# MCU.net
KiCad netlist of a schematic drawn in Altium Designer
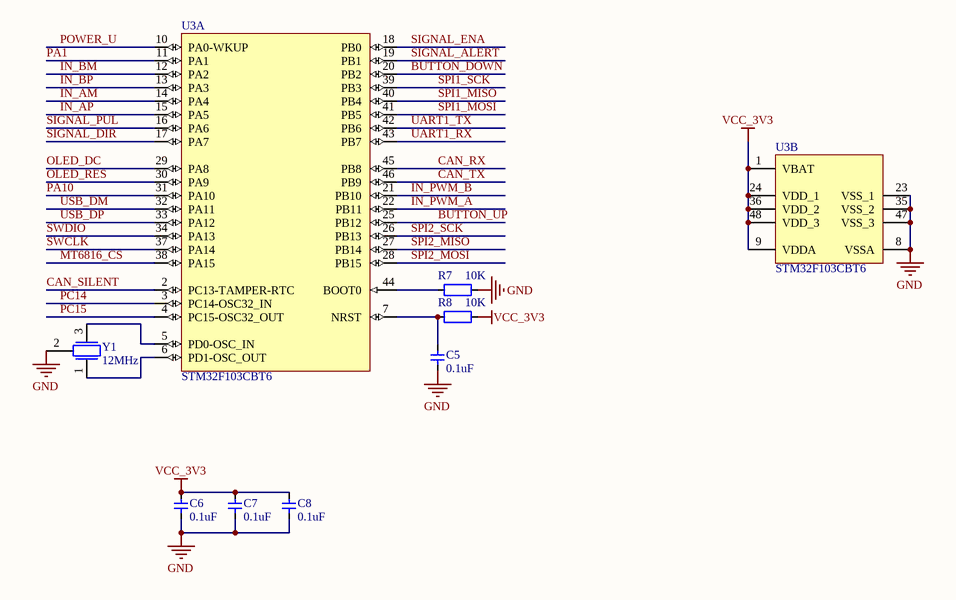
[diagram p0: MCU.SchDoc]

(export (version "E")
  (design (tool "Eeschema 10.0.6"))
  (components
    (comp (ref "C5")
      (value "0.1uF")
      (footprint "CAP_0402")
      (description "Capacitor")
      (libsource (lib "MyPcbLib") (part "电容-0402"))
    )
    (comp (ref "C6")
      (value "0.1uF")
      (footprint "CAP_0402")
      (description "Capacitor")
      (libsource (lib "MyPcbLib") (part "电容-0402"))
    )
    (comp (ref "C7")
      (value "0.1uF")
      (footprint "CAP_0402")
      (description "Capacitor")
      (libsource (lib "MyPcbLib") (part "电容-0402"))
    )
    (comp (ref "C8")
      (value "0.1uF")
      (footprint "CAP_0402")
      (description "Capacitor")
      (libsource (lib "MyPcbLib") (part "电容-0402"))
    )
    (comp (ref "R7")
      (value "10K")
      (footprint "RES_0402")
      (description "Resistor")
      (libsource (lib "MyPcbLib") (part "电阻-0402"))
    )
    (comp (ref "R8")
      (value "10K")
      (footprint "RES_0402")
      (description "Resistor")
      (libsource (lib "MyPcbLib") (part "电阻-0402"))
    )
    (comp (ref "U3")
      (value "STM32F103CBT6")
      (footprint "LQFP-48")
      (libsource (lib "STMicroelectronics STM32 F1") (part "STM32F103CBT6"))
    )
    (comp (ref "Y1")
      (value "12MHz")
      (footprint "晶振-3P")
      (description "村田贴片")
      (libsource (lib "MyPcbLib") (part "晶振-3Pin"))
    )
  )
  (nets
    (net (code "1") (name "/BUTTON_DOWN") (class "Default")
      (node (ref "U3") (pin "20") (pinfunction "PB2_20") (pintype "bidirectional"))
    )
    (net (code "2") (name "/BUTTON_UP") (class "Default")
      (node (ref "U3") (pin "25") (pinfunction "PB12_25") (pintype "bidirectional"))
    )
    (net (code "3") (name "/CAN_RX") (class "Default")
      (node (ref "U3") (pin "45") (pinfunction "PB8_45") (pintype "bidirectional"))
    )
    (net (code "4") (name "/CAN_SILENT") (class "Default")
      (node (ref "U3") (pin "2") (pinfunction "PC13-TAMPER-RTC_2") (pintype "bidirectional"))
    )
    (net (code "5") (name "/CAN_TX") (class "Default")
      (node (ref "U3") (pin "46") (pinfunction "PB9_46") (pintype "bidirectional"))
    )
    (net (code "6") (name "/IN_AM") (class "Default")
      (node (ref "U3") (pin "14") (pinfunction "PA4_14") (pintype "bidirectional"))
    )
    (net (code "7") (name "/IN_AP") (class "Default")
      (node (ref "U3") (pin "15") (pinfunction "PA5_15") (pintype "bidirectional"))
    )
    (net (code "8") (name "/IN_BM") (class "Default")
      (node (ref "U3") (pin "12") (pinfunction "PA2_12") (pintype "bidirectional"))
    )
    (net (code "9") (name "/IN_BP") (class "Default")
      (node (ref "U3") (pin "13") (pinfunction "PA3_13") (pintype "bidirectional"))
    )
    (net (code "10") (name "/IN_PWM_A") (class "Default")
      (node (ref "U3") (pin "22") (pinfunction "PB11_22") (pintype "bidirectional"))
    )
    (net (code "11") (name "/IN_PWM_B") (class "Default")
      (node (ref "U3") (pin "21") (pinfunction "PB10_21") (pintype "bidirectional"))
    )
    (net (code "12") (name "/MT6816_CS") (class "Default")
      (node (ref "U3") (pin "38") (pinfunction "PA15_38") (pintype "bidirectional"))
    )
    (net (code "13") (name "/OLED_DC") (class "Default")
      (node (ref "U3") (pin "29") (pinfunction "PA8_29") (pintype "bidirectional"))
    )
    (net (code "14") (name "/OLED_RES") (class "Default")
      (node (ref "U3") (pin "30") (pinfunction "PA9_30") (pintype "bidirectional"))
    )
    (net (code "15") (name "/PA1") (class "Default")
      (node (ref "U3") (pin "11") (pinfunction "PA1_11") (pintype "bidirectional"))
    )
    (net (code "16") (name "/PA10") (class "Default")
      (node (ref "U3") (pin "31") (pinfunction "PA10_31") (pintype "bidirectional"))
    )
    (net (code "17") (name "/PC14") (class "Default")
      (node (ref "U3") (pin "3") (pinfunction "PC14-OSC32_IN_3") (pintype "bidirectional"))
    )
    (net (code "18") (name "/PC15") (class "Default")
      (node (ref "U3") (pin "4") (pinfunction "PC15-OSC32_OUT_4") (pintype "bidirectional"))
    )
    (net (code "19") (name "/POWER_U") (class "Default")
      (node (ref "U3") (pin "10") (pinfunction "PA0-WKUP_10") (pintype "bidirectional"))
    )
    (net (code "20") (name "/SIGNAL_ALERT") (class "Default")
      (node (ref "U3") (pin "19") (pinfunction "PB1_19") (pintype "bidirectional"))
    )
    (net (code "21") (name "/SIGNAL_DIR") (class "Default")
      (node (ref "U3") (pin "17") (pinfunction "PA7_17") (pintype "bidirectional"))
    )
    (net (code "22") (name "/SIGNAL_ENA") (class "Default")
      (node (ref "U3") (pin "18") (pinfunction "PB0_18") (pintype "bidirectional"))
    )
    (net (code "23") (name "/SIGNAL_PUL") (class "Default")
      (node (ref "U3") (pin "16") (pinfunction "PA6_16") (pintype "bidirectional"))
    )
    (net (code "24") (name "/SPI1_MISO") (class "Default")
      (node (ref "U3") (pin "40") (pinfunction "PB4_40") (pintype "bidirectional"))
    )
    (net (code "25") (name "/SPI1_MOSI") (class "Default")
      (node (ref "U3") (pin "41") (pinfunction "PB5_41") (pintype "bidirectional"))
    )
    (net (code "26") (name "/SPI1_SCK") (class "Default")
      (node (ref "U3") (pin "39") (pinfunction "PB3_39") (pintype "bidirectional"))
    )
    (net (code "27") (name "/SPI2_MISO") (class "Default")
      (node (ref "U3") (pin "27") (pinfunction "PB14_27") (pintype "bidirectional"))
    )
    (net (code "28") (name "/SPI2_MOSI") (class "Default")
      (node (ref "U3") (pin "28") (pinfunction "PB15_28") (pintype "bidirectional"))
    )
    (net (code "29") (name "/SPI2_SCK") (class "Default")
      (node (ref "U3") (pin "26") (pinfunction "PB13_26") (pintype "bidirectional"))
    )
    (net (code "30") (name "/SWCLK") (class "Default")
      (node (ref "U3") (pin "37") (pinfunction "PA14_37") (pintype "bidirectional"))
    )
    (net (code "31") (name "/SWDIO") (class "Default")
      (node (ref "U3") (pin "34") (pinfunction "PA13_34") (pintype "bidirectional"))
    )
    (net (code "32") (name "/UART1_RX") (class "Default")
      (node (ref "U3") (pin "43") (pinfunction "PB7_43") (pintype "bidirectional"))
    )
    (net (code "33") (name "/UART1_TX") (class "Default")
      (node (ref "U3") (pin "42") (pinfunction "PB6_42") (pintype "bidirectional"))
    )
    (net (code "34") (name "/USB_DM") (class "Default")
      (node (ref "U3") (pin "32") (pinfunction "PA11_32") (pintype "bidirectional"))
    )
    (net (code "35") (name "/USB_DP") (class "Default")
      (node (ref "U3") (pin "33") (pinfunction "PA12_33") (pintype "bidirectional"))
    )
    (net (code "36") (name "GND") (class "Default")
      (node (ref "C5") (pin "1") (pinfunction "1_1") (pintype "passive"))
      (node (ref "C6") (pin "1") (pinfunction "1_1") (pintype "passive"))
      (node (ref "C7") (pin "1") (pinfunction "1_1") (pintype "passive"))
      (node (ref "C8") (pin "1") (pinfunction "1_1") (pintype "passive"))
      (node (ref "R7") (pin "2") (pinfunction "2_2") (pintype "passive"))
      (node (ref "U3") (pin "23") (pinfunction "VSS_1_23") (pintype "power_in"))
      (node (ref "U3") (pin "35") (pinfunction "VSS_2_35") (pintype "power_in"))
      (node (ref "U3") (pin "47") (pinfunction "VSS_3_47") (pintype "power_in"))
      (node (ref "U3") (pin "8") (pinfunction "VSSA_8") (pintype "power_in"))
      (node (ref "Y1") (pin "2") (pinfunction "2_2") (pintype "passive"))
    )
    (net (code "37") (name "Net-(U3A-BOOT0)") (class "Default")
      (node (ref "R7") (pin "1") (pinfunction "1_1") (pintype "passive"))
      (node (ref "U3") (pin "44") (pinfunction "BOOT0_44") (pintype "input"))
    )
    (net (code "38") (name "Net-(U3A-NRST)") (class "Default")
      (node (ref "C5") (pin "2") (pinfunction "2_2") (pintype "passive"))
      (node (ref "R8") (pin "1") (pinfunction "1_1") (pintype "passive"))
      (node (ref "U3") (pin "7") (pinfunction "NRST_7") (pintype "bidirectional"))
    )
    (net (code "39") (name "Net-(U3A-PD0-OSC_IN)") (class "Default")
      (node (ref "U3") (pin "5") (pinfunction "PD0-OSC_IN_5") (pintype "bidirectional"))
      (node (ref "Y1") (pin "3") (pinfunction "3_3") (pintype "passive"))
    )
    (net (code "40") (name "Net-(U3A-PD1-OSC_OUT)") (class "Default")
      (node (ref "U3") (pin "6") (pinfunction "PD1-OSC_OUT_6") (pintype "bidirectional"))
      (node (ref "Y1") (pin "1") (pinfunction "1_1") (pintype "passive"))
    )
    (net (code "41") (name "VCC_3V3") (class "Default")
      (node (ref "C6") (pin "2") (pinfunction "2_2") (pintype "passive"))
      (node (ref "C7") (pin "2") (pinfunction "2_2") (pintype "passive"))
      (node (ref "C8") (pin "2") (pinfunction "2_2") (pintype "passive"))
      (node (ref "R8") (pin "2") (pinfunction "2_2") (pintype "passive"))
      (node (ref "U3") (pin "1") (pinfunction "VBAT_1") (pintype "power_in"))
      (node (ref "U3") (pin "24") (pinfunction "VDD_1_24") (pintype "power_in"))
      (node (ref "U3") (pin "36") (pinfunction "VDD_2_36") (pintype "power_in"))
      (node (ref "U3") (pin "48") (pinfunction "VDD_3_48") (pintype "power_in"))
      (node (ref "U3") (pin "9") (pinfunction "VDDA_9") (pintype "power_in"))
    )
  )
)
